# power.net
KiCad netlist of a schematic drawn in Altium Designer
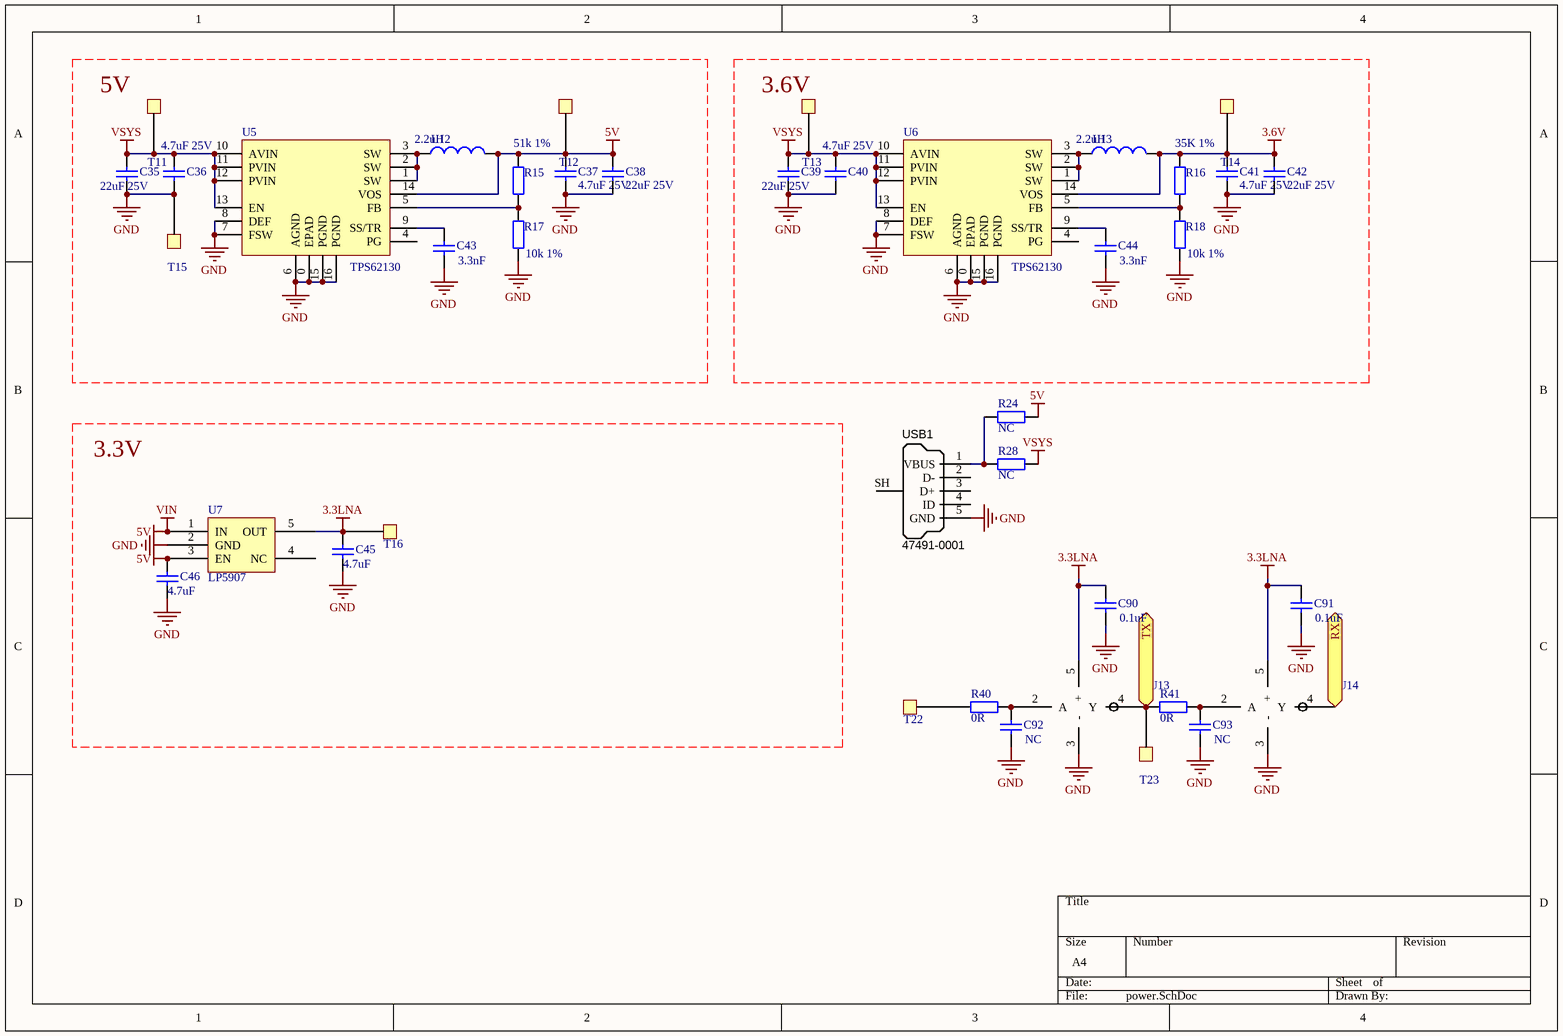
[diagram p0: power.SchDoc]

(export (version "E")
  (design (tool "Eeschema 10.0.6"))
  (components
    (comp (ref "C35")
      (value "22uF 25V")
      (footprint "1210")
      (description "Capacitor")
      (fields (field (name "Comment") "Cap") (field (name "PUBLISHER") "Altium Limited"))
      (libsource (lib "RTC6705") (part "Cap"))
    )
    (comp (ref "C36")
      (value "4.7uF 25V")
      (footprint "0805")
      (description "Capacitor")
      (fields (field (name "Comment") "Cap") (field (name "PUBLISHER") "Altium Limited"))
      (libsource (lib "RTC6705") (part "Cap"))
    )
    (comp (ref "C37")
      (value "4.7uF 25V")
      (footprint "0805")
      (description "Capacitor")
      (fields (field (name "Comment") "Cap") (field (name "PUBLISHER") "Altium Limited"))
      (libsource (lib "RTC6705") (part "Cap"))
    )
    (comp (ref "C38")
      (value "22uF 25V")
      (footprint "1210")
      (description "Capacitor")
      (fields (field (name "Comment") "Cap") (field (name "PUBLISHER") "Altium Limited"))
      (libsource (lib "RTC6705") (part "Cap"))
    )
    (comp (ref "C39")
      (value "22uF 25V")
      (footprint "1210")
      (description "Capacitor")
      (fields (field (name "Comment") "Cap") (field (name "PUBLISHER") "Altium Limited"))
      (libsource (lib "RTC6705") (part "Cap"))
    )
    (comp (ref "C40")
      (value "4.7uF 25V")
      (footprint "0805")
      (description "Capacitor")
      (fields (field (name "Comment") "Cap") (field (name "PUBLISHER") "Altium Limited"))
      (libsource (lib "RTC6705") (part "Cap"))
    )
    (comp (ref "C41")
      (value "4.7uF 25V")
      (footprint "0805")
      (description "Capacitor")
      (fields (field (name "Comment") "Cap") (field (name "PUBLISHER") "Altium Limited"))
      (libsource (lib "RTC6705") (part "Cap"))
    )
    (comp (ref "C42")
      (value "22uF 25V")
      (footprint "1210")
      (description "Capacitor")
      (fields (field (name "Comment") "Cap") (field (name "PUBLISHER") "Altium Limited"))
      (libsource (lib "RTC6705") (part "Cap"))
    )
    (comp (ref "C43")
      (value "3.3nF")
      (footprint "0402")
      (description "Capacitor")
      (fields (field (name "PUBLISHER") "Altium Limited"))
      (libsource (lib "RTC6705") (part "Cap"))
    )
    (comp (ref "C44")
      (value "3.3nF")
      (footprint "0402")
      (description "Capacitor")
      (fields (field (name "PUBLISHER") "Altium Limited"))
      (libsource (lib "RTC6705") (part "Cap"))
    )
    (comp (ref "C45")
      (value "4.7uF")
      (footprint "0603")
      (description "Capacitor")
      (fields (field (name "PUBLISHER") "Altium Limited"))
      (libsource (lib "RTC6705") (part "Cap"))
    )
    (comp (ref "C46")
      (value "4.7uF")
      (footprint "0603")
      (description "Capacitor")
      (fields (field (name "PUBLISHER") "Altium Limited"))
      (libsource (lib "RTC6705") (part "Cap"))
    )
    (comp (ref "C90")
      (value "0.1uF")
      (footprint "0402")
      (description "Capacitor")
      (fields (field (name "PUBLISHER") "Altium Limited"))
      (libsource (lib "RTC6705") (part "Cap"))
    )
    (comp (ref "C91")
      (value "0.1uF")
      (footprint "0402")
      (description "Capacitor")
      (fields (field (name "PUBLISHER") "Altium Limited"))
      (libsource (lib "RTC6705") (part "Cap"))
    )
    (comp (ref "C92")
      (value "NC")
      (footprint "0402")
      (description "Capacitor")
      (fields (field (name "PUBLISHER") "Altium Limited"))
      (libsource (lib "RTC6705") (part "Cap"))
    )
    (comp (ref "C93")
      (value "NC")
      (footprint "0402")
      (description "Capacitor")
      (fields (field (name "PUBLISHER") "Altium Limited"))
      (libsource (lib "RTC6705") (part "Cap"))
    )
    (comp (ref "L12")
      (value "2.2uH")
      (footprint "L3015")
      (description "Inductor")
      (fields (field (name "PUBLISHER") "Altium Limited"))
      (libsource (lib "Miscellaneous Devices") (part "Inductor"))
    )
    (comp (ref "L13")
      (value "2.2uH")
      (footprint "L3015")
      (description "Inductor")
      (fields (field (name "PUBLISHER") "Altium Limited"))
      (libsource (lib "Miscellaneous Devices") (part "Inductor"))
    )
    (comp (ref "R15")
      (value "51k 1%")
      (footprint "0402")
      (description "Resistor")
      (fields (field (name "PUBLISHER") "Altium Limited"))
      (libsource (lib "") (part "Res2_1"))
    )
    (comp (ref "R16")
      (value "35K 1%")
      (footprint "0402")
      (description "Resistor")
      (fields (field (name "PUBLISHER") "Altium Limited"))
      (libsource (lib "") (part "Res2_1"))
    )
    (comp (ref "R17")
      (value "10k 1%")
      (footprint "0402")
      (description "Resistor")
      (fields (field (name "PUBLISHER") "Altium Limited"))
      (libsource (lib "") (part "Res2_1"))
    )
    (comp (ref "R18")
      (value "10k 1%")
      (footprint "0402")
      (description "Resistor")
      (fields (field (name "PUBLISHER") "Altium Limited"))
      (libsource (lib "") (part "Res2_1"))
    )
    (comp (ref "R24")
      (value "NC")
      (footprint "0603")
      (description "Resistor")
      (fields (field (name "PUBLISHER") "Altium Limited"))
      (libsource (lib "RTC6705") (part "Res2"))
    )
    (comp (ref "R28")
      (value "NC")
      (footprint "0603")
      (description "Resistor")
      (fields (field (name "PUBLISHER") "Altium Limited"))
      (libsource (lib "RTC6705") (part "Res2"))
    )
    (comp (ref "R40")
      (value "0R")
      (footprint "0402")
      (description "Resistor")
      (fields (field (name "PUBLISHER") "Altium Limited"))
      (libsource (lib "RTC6705") (part "Res2"))
    )
    (comp (ref "R41")
      (value "0R")
      (footprint "0402")
      (description "Resistor")
      (fields (field (name "PUBLISHER") "Altium Limited"))
      (libsource (lib "RTC6705") (part "Res2"))
    )
    (comp (ref "T11") (value "TestPad") (footprint "TestPad") (libsource (lib "sch") (part "TestPad")))
    (comp (ref "T12") (value "TestPad") (footprint "TestPad - 1mm") (libsource (lib "sch") (part "TestPad")))
    (comp (ref "T13") (value "TestPad") (footprint "TestPad - 1mm") (libsource (lib "sch") (part "TestPad")))
    (comp (ref "T14") (value "TestPad") (footprint "TestPad - 1mm") (libsource (lib "sch") (part "TestPad")))
    (comp (ref "T15") (value "TestPad") (footprint "TestPad") (libsource (lib "") (part "TestPad_1")))
    (comp (ref "T16") (value "TestPad") (footprint "TestPad - 1mm") (libsource (lib "") (part "TestPad_2")))
    (comp (ref "T22") (value "TestPad") (footprint "TestPad") (libsource (lib "") (part "TestPad_3")))
    (comp (ref "T23") (value "TestPad") (footprint "TestPad") (libsource (lib "") (part "TestPad_1")))
    (comp (ref "U5") (value "TPS62130") (footprint "TPS62130") (libsource (lib "sch") (part "TPS62130")))
    (comp (ref "U6") (value "TPS62130") (footprint "TPS62130") (libsource (lib "sch") (part "TPS62130")))
    (comp (ref "U7") (value "LP5907") (footprint "SOT23-5") (libsource (lib "RTC6705") (part "LP5907")))
    (comp (ref "U13")
      (value "INVERTER-SOT23")
      (footprint "SOT23-5")
      (libsource (lib "sch") (part "INVERTER-SOT23"))
    )
    (comp (ref "U14")
      (value "INVERTER-SOT23")
      (footprint "SOT23-5")
      (libsource (lib "sch") (part "INVERTER-SOT23"))
    )
    (comp (ref "USB1")
      (value "USB Micro Type B")
      (footprint "MICRO-YZX")
      (description "Connector SMD USB Micro Type B middle mount")
      (fields (field (name "MANUFACTURER PART NUMBER 1") "47491-0001"))
      (libsource (lib "PBL - Connectors") (part "USB_Micro_TypeB"))
    )
  )
  (nets
    (net (code "1") (name "/RX") (class "Default")
      (node (ref "U14") (pin "4") (pinfunction "Y_4") (pintype "passive"))
    )
    (net (code "2") (name "/TX") (class "Default")
      (node (ref "R41") (pin "1") (pinfunction "1_1") (pintype "passive"))
      (node (ref "T23") (pin "1") (pinfunction "3_1") (pintype "passive"))
      (node (ref "U13") (pin "4") (pinfunction "Y_4") (pintype "passive"))
    )
    (net (code "3") (name "3.3LNA") (class "Default")
      (node (ref "C45") (pin "2") (pinfunction "2_2") (pintype "passive"))
      (node (ref "C90") (pin "1") (pinfunction "1_1") (pintype "passive"))
      (node (ref "C91") (pin "1") (pinfunction "1_1") (pintype "passive"))
      (node (ref "T16") (pin "1") (pinfunction "3_1") (pintype "passive"))
      (node (ref "U13") (pin "5") (pinfunction "+_5") (pintype "passive"))
      (node (ref "U14") (pin "5") (pinfunction "+_5") (pintype "passive"))
      (node (ref "U7") (pin "5") (pinfunction "OUT_5") (pintype "passive"))
    )
    (net (code "4") (name "3.6V") (class "Default")
      (node (ref "C41") (pin "2") (pinfunction "2_2") (pintype "passive"))
      (node (ref "C42") (pin "2") (pinfunction "2_2") (pintype "passive"))
      (node (ref "L13") (pin "2") (pinfunction "2_2") (pintype "passive"))
      (node (ref "R16") (pin "1") (pinfunction "1_1") (pintype "passive"))
      (node (ref "T14") (pin "1") (pinfunction "3_1") (pintype "passive"))
      (node (ref "U6") (pin "14") (pinfunction "VOS_14") (pintype "passive"))
    )
    (net (code "5") (name "5V") (class "Default")
      (node (ref "C37") (pin "2") (pinfunction "2_2") (pintype "passive"))
      (node (ref "C38") (pin "2") (pinfunction "2_2") (pintype "passive"))
      (node (ref "C46") (pin "2") (pinfunction "2_2") (pintype "passive"))
      (node (ref "L12") (pin "2") (pinfunction "2_2") (pintype "passive"))
      (node (ref "R15") (pin "1") (pinfunction "1_1") (pintype "passive"))
      (node (ref "R24") (pin "2") (pinfunction "2_2") (pintype "passive"))
      (node (ref "T12") (pin "1") (pinfunction "3_1") (pintype "passive"))
      (node (ref "U5") (pin "14") (pinfunction "VOS_14") (pintype "passive"))
      (node (ref "U7") (pin "1") (pinfunction "IN_1") (pintype "passive"))
      (node (ref "U7") (pin "3") (pinfunction "EN_3") (pintype "passive"))
    )
    (net (code "6") (name "GND") (class "Default")
      (node (ref "C35") (pin "2") (pinfunction "2_2") (pintype "passive"))
      (node (ref "C36") (pin "2") (pinfunction "2_2") (pintype "passive"))
      (node (ref "C37") (pin "1") (pinfunction "1_1") (pintype "passive"))
      (node (ref "C38") (pin "1") (pinfunction "1_1") (pintype "passive"))
      (node (ref "C39") (pin "2") (pinfunction "2_2") (pintype "passive"))
      (node (ref "C40") (pin "2") (pinfunction "2_2") (pintype "passive"))
      (node (ref "C41") (pin "1") (pinfunction "1_1") (pintype "passive"))
      (node (ref "C42") (pin "1") (pinfunction "1_1") (pintype "passive"))
      (node (ref "C43") (pin "2") (pinfunction "2_2") (pintype "passive"))
      (node (ref "C44") (pin "2") (pinfunction "2_2") (pintype "passive"))
      (node (ref "C45") (pin "1") (pinfunction "1_1") (pintype "passive"))
      (node (ref "C46") (pin "1") (pinfunction "1_1") (pintype "passive"))
      (node (ref "C90") (pin "2") (pinfunction "2_2") (pintype "passive"))
      (node (ref "C91") (pin "2") (pinfunction "2_2") (pintype "passive"))
      (node (ref "C92") (pin "2") (pinfunction "2_2") (pintype "passive"))
      (node (ref "C93") (pin "2") (pinfunction "2_2") (pintype "passive"))
      (node (ref "R17") (pin "2") (pinfunction "2_2") (pintype "passive"))
      (node (ref "R18") (pin "2") (pinfunction "2_2") (pintype "passive"))
      (node (ref "T15") (pin "1") (pinfunction "3_1") (pintype "passive"))
      (node (ref "U13") (pin "3") (pinfunction "-_3") (pintype "passive"))
      (node (ref "U14") (pin "3") (pinfunction "-_3") (pintype "passive"))
      (node (ref "U5") (pin "0") (pinfunction "EPAD_0") (pintype "passive"))
      (node (ref "U5") (pin "15") (pinfunction "PGND_15") (pintype "passive"))
      (node (ref "U5") (pin "16") (pinfunction "PGND_16") (pintype "passive"))
      (node (ref "U5") (pin "6") (pinfunction "AGND_6") (pintype "passive"))
      (node (ref "U5") (pin "7") (pinfunction "FSW_7") (pintype "passive"))
      (node (ref "U5") (pin "8") (pinfunction "DEF_8") (pintype "passive"))
      (node (ref "U6") (pin "0") (pinfunction "EPAD_0") (pintype "passive"))
      (node (ref "U6") (pin "15") (pinfunction "PGND_15") (pintype "passive"))
      (node (ref "U6") (pin "16") (pinfunction "PGND_16") (pintype "passive"))
      (node (ref "U6") (pin "6") (pinfunction "AGND_6") (pintype "passive"))
      (node (ref "U6") (pin "7") (pinfunction "FSW_7") (pintype "passive"))
      (node (ref "U6") (pin "8") (pinfunction "DEF_8") (pintype "passive"))
      (node (ref "U7") (pin "2") (pinfunction "GND_2") (pintype "passive"))
      (node (ref "USB1") (pin "5") (pinfunction "GND_5") (pintype "passive"))
    )
    (net (code "7") (name "Net-(L12-Pad1)") (class "Default")
      (node (ref "L12") (pin "1") (pinfunction "1_1") (pintype "passive"))
      (node (ref "U5") (pin "1") (pinfunction "SW_1") (pintype "passive"))
      (node (ref "U5") (pin "2") (pinfunction "SW_2") (pintype "passive"))
      (node (ref "U5") (pin "3") (pinfunction "SW_3") (pintype "passive"))
    )
    (net (code "8") (name "Net-(L13-Pad1)") (class "Default")
      (node (ref "L13") (pin "1") (pinfunction "1_1") (pintype "passive"))
      (node (ref "U6") (pin "1") (pinfunction "SW_1") (pintype "passive"))
      (node (ref "U6") (pin "2") (pinfunction "SW_2") (pintype "passive"))
      (node (ref "U6") (pin "3") (pinfunction "SW_3") (pintype "passive"))
    )
    (net (code "9") (name "Net-(T22-3)") (class "Default")
      (node (ref "R40") (pin "1") (pinfunction "1_1") (pintype "passive"))
      (node (ref "T22") (pin "1") (pinfunction "3_1") (pintype "passive"))
    )
    (net (code "10") (name "Net-(U5-FB)") (class "Default")
      (node (ref "R15") (pin "2") (pinfunction "2_2") (pintype "passive"))
      (node (ref "R17") (pin "1") (pinfunction "1_1") (pintype "passive"))
      (node (ref "U5") (pin "5") (pinfunction "FB_5") (pintype "passive"))
    )
    (net (code "11") (name "Net-(U5-SS{slash}TR)") (class "Default")
      (node (ref "C43") (pin "1") (pinfunction "1_1") (pintype "passive"))
      (node (ref "U5") (pin "9") (pinfunction "SS/TR_9") (pintype "passive"))
    )
    (net (code "12") (name "Net-(U6-FB)") (class "Default")
      (node (ref "R16") (pin "2") (pinfunction "2_2") (pintype "passive"))
      (node (ref "R18") (pin "1") (pinfunction "1_1") (pintype "passive"))
      (node (ref "U6") (pin "5") (pinfunction "FB_5") (pintype "passive"))
    )
    (net (code "13") (name "Net-(U6-SS{slash}TR)") (class "Default")
      (node (ref "C44") (pin "1") (pinfunction "1_1") (pintype "passive"))
      (node (ref "U6") (pin "9") (pinfunction "SS/TR_9") (pintype "passive"))
    )
    (net (code "14") (name "Net-(U13-A)") (class "Default")
      (node (ref "C92") (pin "1") (pinfunction "1_1") (pintype "passive"))
      (node (ref "R40") (pin "2") (pinfunction "2_2") (pintype "passive"))
      (node (ref "U13") (pin "2") (pinfunction "A_2") (pintype "passive"))
    )
    (net (code "15") (name "Net-(U14-A)") (class "Default")
      (node (ref "C93") (pin "1") (pinfunction "1_1") (pintype "passive"))
      (node (ref "R41") (pin "2") (pinfunction "2_2") (pintype "passive"))
      (node (ref "U14") (pin "2") (pinfunction "A_2") (pintype "passive"))
    )
    (net (code "16") (name "Net-(USB1-VBUS)") (class "Default")
      (node (ref "R24") (pin "1") (pinfunction "1_1") (pintype "passive"))
      (node (ref "R28") (pin "1") (pinfunction "1_1") (pintype "passive"))
      (node (ref "USB1") (pin "1") (pinfunction "VBUS_1") (pintype "passive"))
    )
    (net (code "17") (name "VSYS") (class "Default")
      (node (ref "C35") (pin "1") (pinfunction "1_1") (pintype "passive"))
      (node (ref "C36") (pin "1") (pinfunction "1_1") (pintype "passive"))
      (node (ref "C39") (pin "1") (pinfunction "1_1") (pintype "passive"))
      (node (ref "C40") (pin "1") (pinfunction "1_1") (pintype "passive"))
      (node (ref "R28") (pin "2") (pinfunction "2_2") (pintype "passive"))
      (node (ref "T11") (pin "1") (pinfunction "3_1") (pintype "passive"))
      (node (ref "T13") (pin "1") (pinfunction "3_1") (pintype "passive"))
      (node (ref "U5") (pin "10") (pinfunction "AVIN_10") (pintype "passive"))
      (node (ref "U5") (pin "11") (pinfunction "PVIN_11") (pintype "passive"))
      (node (ref "U5") (pin "12") (pinfunction "PVIN_12") (pintype "passive"))
      (node (ref "U5") (pin "13") (pinfunction "EN_13") (pintype "passive"))
      (node (ref "U6") (pin "10") (pinfunction "AVIN_10") (pintype "passive"))
      (node (ref "U6") (pin "11") (pinfunction "PVIN_11") (pintype "passive"))
      (node (ref "U6") (pin "12") (pinfunction "PVIN_12") (pintype "passive"))
      (node (ref "U6") (pin "13") (pinfunction "EN_13") (pintype "passive"))
    )
    (net (code "18") (name "unconnected-(U5-PG-Pad4)") (class "Default")
      (node (ref "U5") (pin "4") (pinfunction "PG_4") (pintype "passive"))
    )
    (net (code "19") (name "unconnected-(U6-PG-Pad4)") (class "Default")
      (node (ref "U6") (pin "4") (pinfunction "PG_4") (pintype "passive"))
    )
    (net (code "20") (name "unconnected-(U7-NC-Pad4)") (class "Default")
      (node (ref "U7") (pin "4") (pinfunction "NC_4") (pintype "passive"))
    )
    (net (code "21") (name "unconnected-(USB1-D+-Pad3)") (class "Default")
      (node (ref "USB1") (pin "3") (pinfunction "D+_3") (pintype "passive"))
    )
    (net (code "22") (name "unconnected-(USB1-D--Pad2)") (class "Default")
      (node (ref "USB1") (pin "2") (pinfunction "D-_2") (pintype "passive"))
    )
    (net (code "23") (name "unconnected-(USB1-ID-Pad4)") (class "Default")
      (node (ref "USB1") (pin "4") (pinfunction "ID_4") (pintype "passive"))
    )
    (net (code "24") (name "unconnected-(USB1-Shell-PadSH)") (class "Default")
      (node (ref "USB1") (pin "SH") (pinfunction "Shell_SH") (pintype "passive"))
    )
  )
)
